# full_schematic.net
KiCad netlist of a schematic drawn in EAGLE
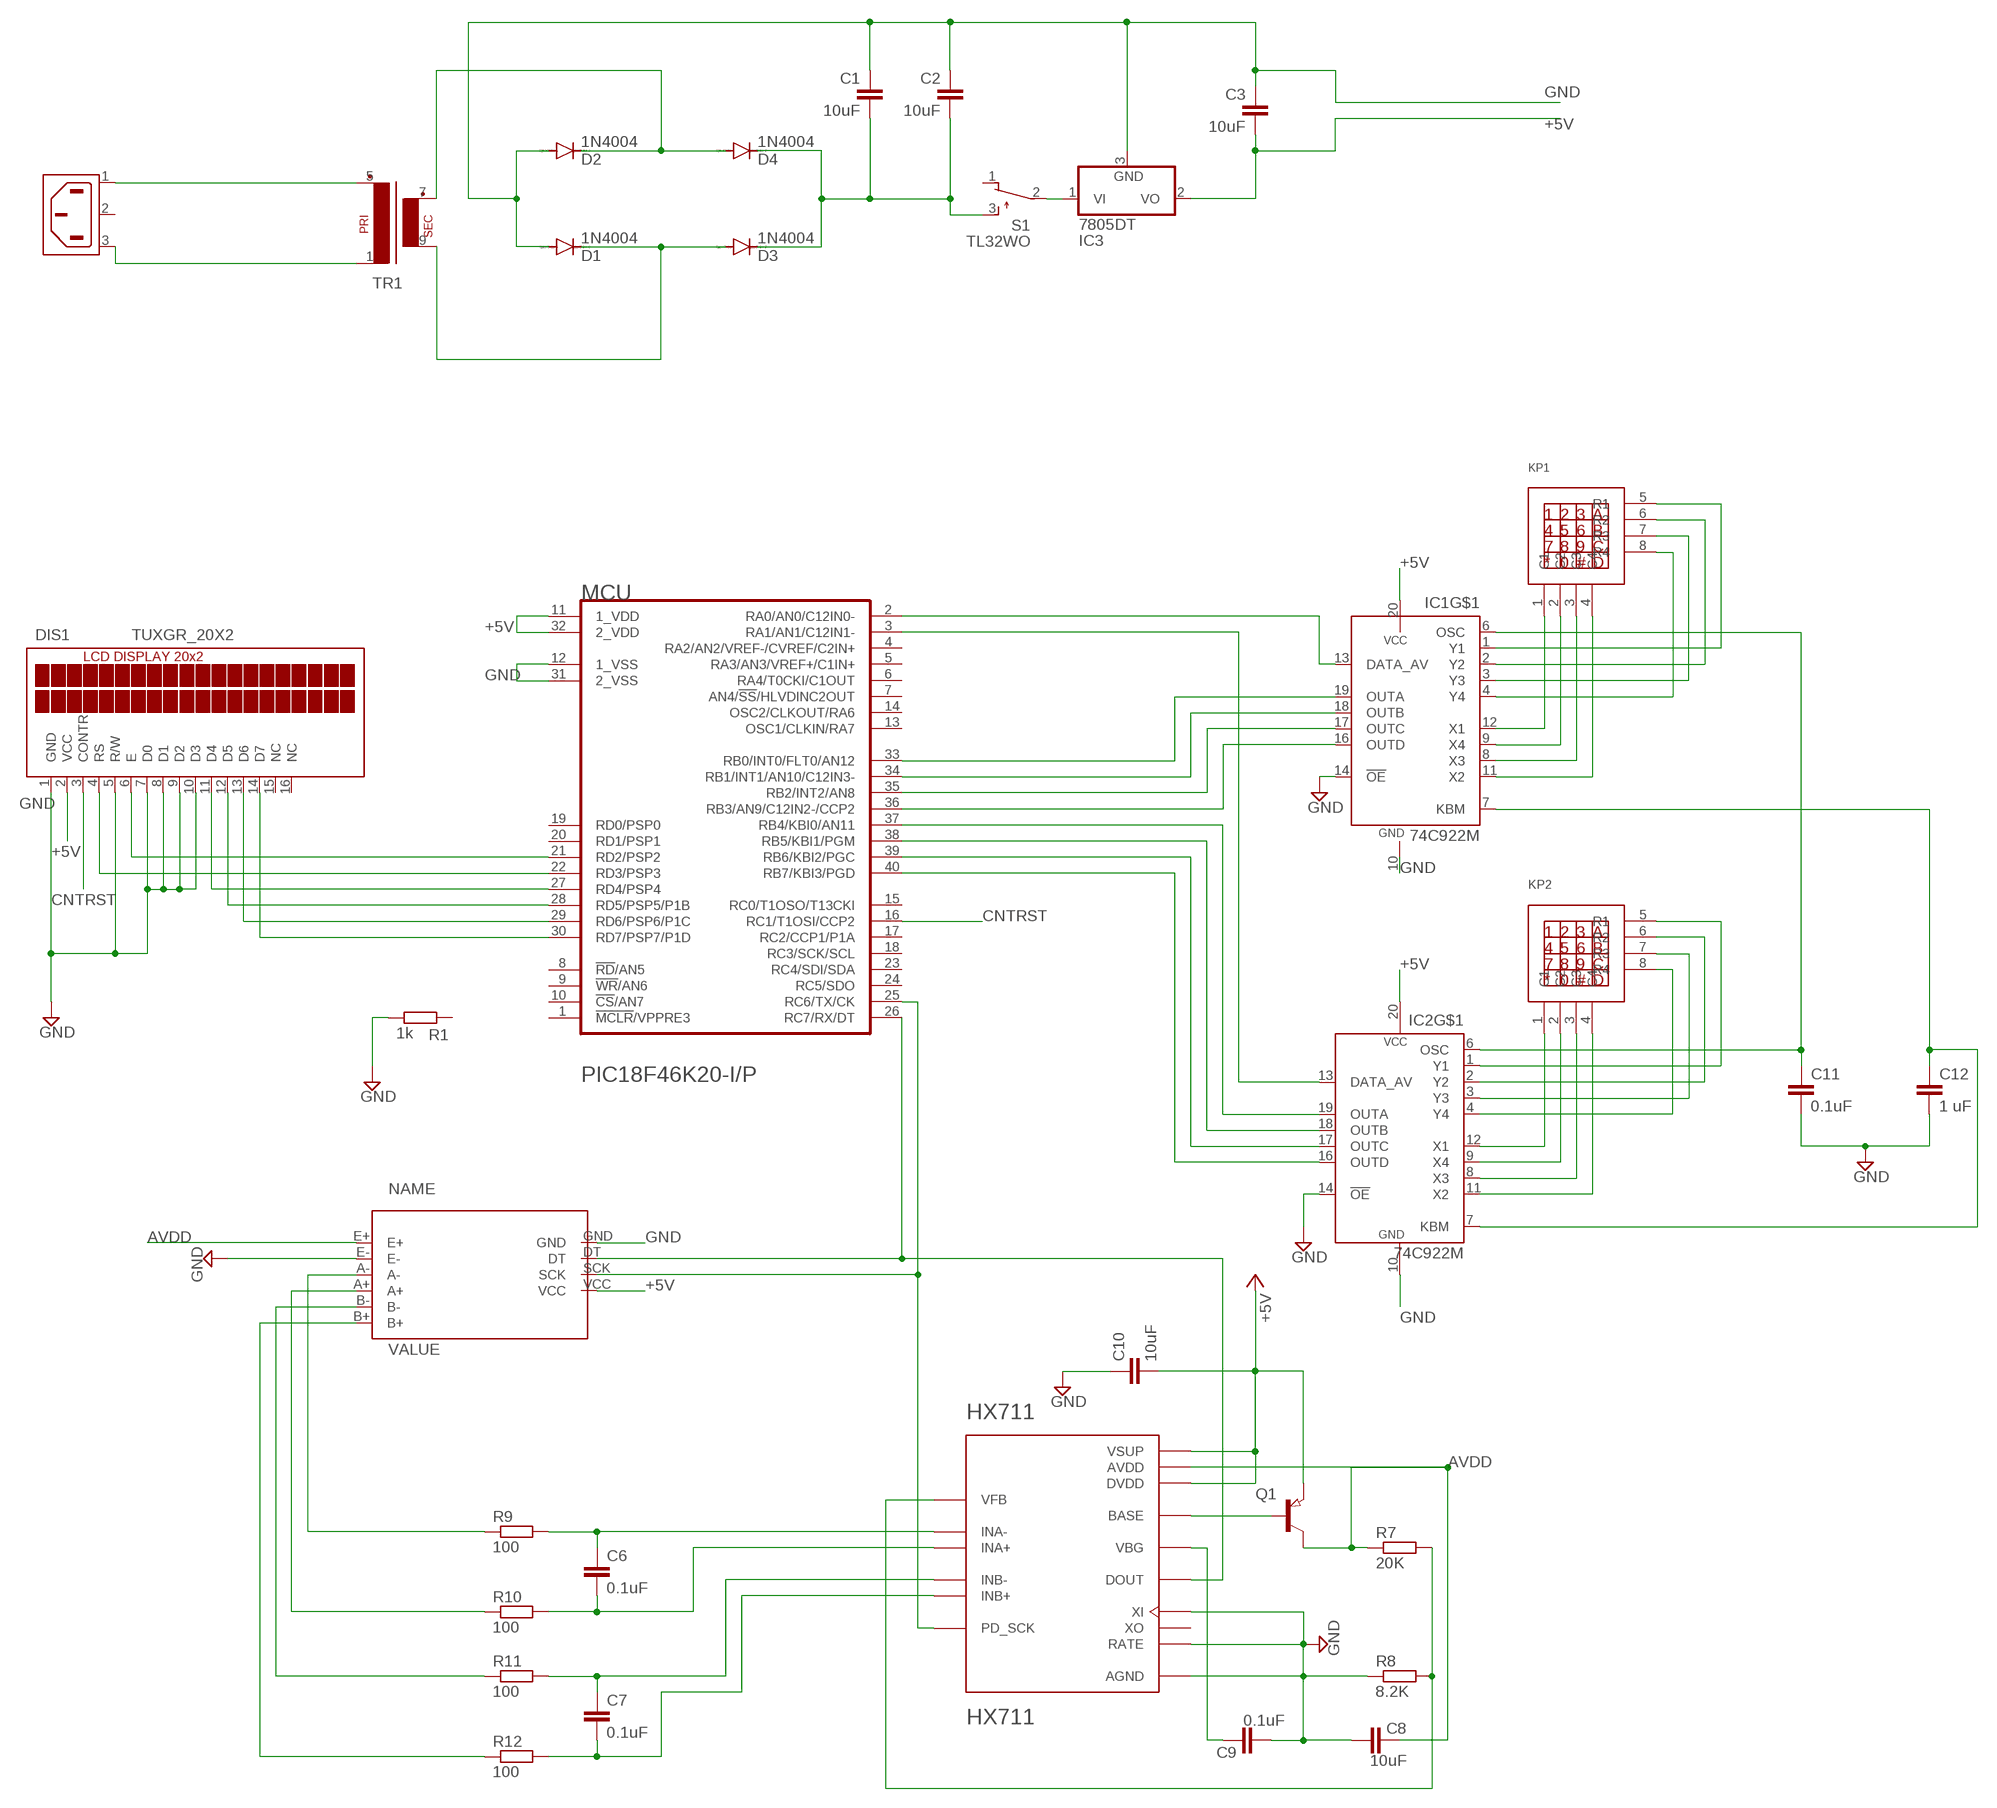
[diagram p0: schematic, sheet 1]

(export (version "E")
  (design (tool "Eeschema 10.0.6"))
  (components
    (comp (ref "C1")
      (value "10uF")
      (footprint "eagle-import:C2.5-2")
      (libsource (lib "eagle-import") (part "C2.5/2"))
    )
    (comp (ref "C2")
      (value "10uF")
      (footprint "eagle-import:C2.5-2")
      (libsource (lib "eagle-import") (part "C2.5/2"))
    )
    (comp (ref "C3")
      (value "10uF")
      (footprint "eagle-import:C2.5-2")
      (libsource (lib "eagle-import") (part "C2.5/2"))
    )
    (comp (ref "C6")
      (value "0.1uF")
      (footprint "eagle-import:C2.5-2")
      (libsource (lib "eagle-import") (part "C2.5/2"))
    )
    (comp (ref "C7")
      (value "0.1uF")
      (footprint "eagle-import:C2.5-2")
      (libsource (lib "eagle-import") (part "C2.5/2"))
    )
    (comp (ref "C8")
      (value "10uF")
      (footprint "eagle-import:C2.5-2")
      (libsource (lib "eagle-import") (part "C2.5/2"))
    )
    (comp (ref "C9")
      (value "0.1uF")
      (footprint "eagle-import:C2.5-2")
      (libsource (lib "eagle-import") (part "C2.5/2"))
    )
    (comp (ref "C10")
      (value "10uF")
      (footprint "eagle-import:C2.5-2")
      (libsource (lib "eagle-import") (part "C2.5/2"))
    )
    (comp (ref "C11")
      (value "0.1uF")
      (footprint "eagle-import:C2.5-2")
      (libsource (lib "eagle-import") (part "C2.5/2"))
    )
    (comp (ref "C12")
      (value "1 uF")
      (footprint "eagle-import:C2.5-2")
      (libsource (lib "eagle-import") (part "C2.5/2"))
    )
    (comp (ref "D1")
      (value "1N4004")
      (footprint "eagle-import:DO41-10")
      (libsource (lib "eagle-import") (part "1N4004"))
    )
    (comp (ref "D2")
      (value "1N4004")
      (footprint "eagle-import:DO41-10")
      (libsource (lib "eagle-import") (part "1N4004"))
    )
    (comp (ref "D3")
      (value "1N4004")
      (footprint "eagle-import:DO41-10")
      (libsource (lib "eagle-import") (part "1N4004"))
    )
    (comp (ref "D4")
      (value "1N4004")
      (footprint "eagle-import:DO41-10")
      (libsource (lib "eagle-import") (part "1N4004"))
    )
    (comp (ref "DIS1")
      (value "TUXGR_20X2")
      (footprint "eagle-import:TUXGR_20X2")
      (libsource (lib "eagle-import") (part "TUXGR_20X2"))
    )
    (comp (ref "HX711")
      (value "HX711")
      (footprint "eagle-import:SOP127P600X180-16N")
      (fields (field (name "MF") "AVIA SEMICONDUCTOR"))
      (libsource (lib "eagle-import") (part "HX711"))
    )
    (comp (ref "HX711MODULE")
      (value "hx")
      (footprint "eagle-import:HX711")
      (libsource (lib "eagle-import") (part "HX711A"))
    )
    (comp (ref "IC1")
      (value "74C922M")
      (footprint "eagle-import:SO20W")
      (libsource (lib "eagle-import") (part "74C922M"))
    )
    (comp (ref "IC2")
      (value "74C922M")
      (footprint "eagle-import:SO20W")
      (libsource (lib "eagle-import") (part "74C922M"))
    )
    (comp (ref "IC3")
      (value "7805DT")
      (footprint "eagle-import:TO252")
      (libsource (lib "eagle-import") (part "78DT05"))
    )
    (comp (ref "KP1")
      (value "KEYPAD4X4")
      (footprint "eagle-import:KEYPAD4X4")
      (libsource (lib "eagle-import") (part "KEYPAD4X4"))
    )
    (comp (ref "KP2")
      (value "KEYPAD4X4")
      (footprint "eagle-import:KEYPAD4X4")
      (libsource (lib "eagle-import") (part "KEYPAD4X4"))
    )
    (comp (ref "MCU")
      (value "MICROCHIP_PIC18F46K20-I-PMICROCHIP_PIC18F46K20-I-P_0_0")
      (footprint "eagle-import:MICROCHIP_PIC18F46K20-I-P_0")
      (fields (field (name "MF") "Microchip") (field (name "MPN") "PIC18F46K20-I/P"))
      (libsource (lib "eagle-import") (part "MICROCHIP_PIC18F46K20-I-PMICROCHIP_PIC18F46K20-I-P_0_0"))
    )
    (comp (ref "Q1")
      (value "PNP-TRANSISTOR_SOT23")
      (footprint "eagle-import:SOT23")
      (libsource (lib "eagle-import") (part "PNP-TRANSISTOR_SOT23"))
    )
    (comp (ref "R1")
      (value "1k")
      (footprint "eagle-import:R0603")
      (libsource (lib "eagle-import") (part "R-EU_R0603"))
    )
    (comp (ref "R7")
      (value "20K")
      (footprint "eagle-import:R0603")
      (libsource (lib "eagle-import") (part "R-EU_R0603"))
    )
    (comp (ref "R8")
      (value "8.2K")
      (footprint "eagle-import:R0603")
      (libsource (lib "eagle-import") (part "R-EU_R0603"))
    )
    (comp (ref "R9")
      (value "100")
      (footprint "eagle-import:R0603")
      (libsource (lib "eagle-import") (part "R-EU_R0603"))
    )
    (comp (ref "R10")
      (value "100")
      (footprint "eagle-import:R0603")
      (libsource (lib "eagle-import") (part "R-EU_R0603"))
    )
    (comp (ref "R11")
      (value "100")
      (footprint "eagle-import:R0603")
      (libsource (lib "eagle-import") (part "R-EU_R0603"))
    )
    (comp (ref "R12")
      (value "100")
      (footprint "eagle-import:R0603")
      (libsource (lib "eagle-import") (part "R-EU_R0603"))
    )
    (comp (ref "S1")
      (value "TL32WO")
      (footprint "eagle-import:TL3XWO")
      (libsource (lib "eagle-import") (part "TL32WO"))
    )
    (comp (ref "TR1")
      (value "EI30-1")
      (footprint "eagle-import:EI30-1")
      (libsource (lib "eagle-import") (part "EI30-1"))
    )
    (comp (ref "X1")
      (value "6ESRM-P")
      (footprint "eagle-import:6ESRM-P")
      (fields (field (name "MF") "TYCO ELECTRONICS"))
      (libsource (lib "eagle-import") (part "6ESRM-P"))
    )
  )
  (nets
    (net (code "1") (name "+5V") (class "Default")
      (node (ref "C10") (pin "2") (pinfunction "2_2") (pintype "passive"))
      (node (ref "C3") (pin "2") (pinfunction "2_2") (pintype "passive"))
      (node (ref "DIS1") (pin "2") (pinfunction "VCC_2") (pintype "power_in"))
      (node (ref "HX711") (pin "1") (pinfunction "VSUP_1") (pintype "power_in"))
      (node (ref "HX711") (pin "16") (pinfunction "DVDD_16") (pintype "power_in"))
      (node (ref "HX711MODULE") (pin "VCC") (pinfunction "VCC_VCC") (pintype "bidirectional"))
      (node (ref "IC1") (pin "20") (pinfunction "VCC_20") (pintype "power_in"))
      (node (ref "IC2") (pin "20") (pinfunction "VCC_20") (pintype "power_in"))
      (node (ref "IC3") (pin "2") (pinfunction "VO_2") (pintype "passive"))
      (node (ref "MCU") (pin "11") (pinfunction "1_VDD_11") (pintype "power_in"))
      (node (ref "MCU") (pin "32") (pinfunction "2_VDD_32") (pintype "power_in"))
      (node (ref "Q1") (pin "2") (pinfunction "E_2") (pintype "passive"))
    )
    (net (code "2") (name "/AVDD") (class "Default")
      (node (ref "C8") (pin "1") (pinfunction "1_1") (pintype "passive"))
      (node (ref "HX711") (pin "3") (pinfunction "AVDD_3") (pintype "power_in"))
      (node (ref "HX711MODULE") (pin "E+") (pinfunction "E+_E+") (pintype "bidirectional"))
      (node (ref "Q1") (pin "3") (pinfunction "C_3") (pintype "passive"))
      (node (ref "R7") (pin "1") (pinfunction "1_1") (pintype "passive"))
    )
    (net (code "3") (name "/CNTRST") (class "Default")
      (node (ref "DIS1") (pin "3") (pinfunction "CONTR_3") (pintype "input"))
      (node (ref "MCU") (pin "16") (pinfunction "RC1/T1OSI/CCP2_16") (pintype "bidirectional"))
    )
    (net (code "4") (name "GND") (class "Default")
      (node (ref "C1") (pin "1") (pinfunction "1_1") (pintype "passive"))
      (node (ref "C10") (pin "1") (pinfunction "1_1") (pintype "passive"))
      (node (ref "C11") (pin "2") (pinfunction "2_2") (pintype "passive"))
      (node (ref "C12") (pin "2") (pinfunction "2_2") (pintype "passive"))
      (node (ref "C2") (pin "1") (pinfunction "1_1") (pintype "passive"))
      (node (ref "C3") (pin "1") (pinfunction "1_1") (pintype "passive"))
      (node (ref "C8") (pin "2") (pinfunction "2_2") (pintype "passive"))
      (node (ref "C9") (pin "2") (pinfunction "2_2") (pintype "passive"))
      (node (ref "D1") (pin "A") (pinfunction "A_A") (pintype "passive"))
      (node (ref "D2") (pin "A") (pinfunction "A_A") (pintype "passive"))
      (node (ref "DIS1") (pin "1") (pinfunction "GND_1") (pintype "power_in"))
      (node (ref "DIS1") (pin "10") (pinfunction "D3_10") (pintype "input"))
      (node (ref "DIS1") (pin "5") (pinfunction "R/W_5") (pintype "input"))
      (node (ref "DIS1") (pin "7") (pinfunction "D0_7") (pintype "input"))
      (node (ref "DIS1") (pin "8") (pinfunction "D1_8") (pintype "input"))
      (node (ref "DIS1") (pin "9") (pinfunction "D2_9") (pintype "input"))
      (node (ref "HX711") (pin "14") (pinfunction "XI_14") (pintype "input"))
      (node (ref "HX711") (pin "15") (pinfunction "RATE_15") (pintype "input"))
      (node (ref "HX711") (pin "5") (pinfunction "AGND_5") (pintype "power_in"))
      (node (ref "HX711MODULE") (pin "E-") (pinfunction "E-_E-") (pintype "bidirectional"))
      (node (ref "HX711MODULE") (pin "GND") (pinfunction "GND_GND") (pintype "bidirectional"))
      (node (ref "IC1") (pin "10") (pinfunction "GND_10") (pintype "power_in"))
      (node (ref "IC1") (pin "14") (pinfunction "~{OE}_14") (pintype "input"))
      (node (ref "IC2") (pin "10") (pinfunction "GND_10") (pintype "power_in"))
      (node (ref "IC2") (pin "14") (pinfunction "~{OE}_14") (pintype "input"))
      (node (ref "IC3") (pin "3") (pinfunction "GND_3") (pintype "passive"))
      (node (ref "MCU") (pin "12") (pinfunction "1_VSS_12") (pintype "power_in"))
      (node (ref "MCU") (pin "31") (pinfunction "2_VSS_31") (pintype "power_in"))
      (node (ref "R1") (pin "1") (pinfunction "1_1") (pintype "passive"))
      (node (ref "R8") (pin "1") (pinfunction "1_1") (pintype "passive"))
    )
    (net (code "5") (name "Net-(DIS1-D4)") (class "Default")
      (node (ref "DIS1") (pin "11") (pinfunction "D4_11") (pintype "input"))
      (node (ref "MCU") (pin "27") (pinfunction "RD4/PSP4_27") (pintype "bidirectional"))
    )
    (net (code "6") (name "Net-(DIS1-D5)") (class "Default")
      (node (ref "DIS1") (pin "12") (pinfunction "D5_12") (pintype "input"))
      (node (ref "MCU") (pin "28") (pinfunction "RD5/PSP5/P1B_28") (pintype "bidirectional"))
    )
    (net (code "7") (name "Net-(DIS1-D6)") (class "Default")
      (node (ref "DIS1") (pin "13") (pinfunction "D6_13") (pintype "input"))
      (node (ref "MCU") (pin "29") (pinfunction "RD6/PSP6/P1C_29") (pintype "bidirectional"))
    )
    (net (code "8") (name "Net-(DIS1-D7)") (class "Default")
      (node (ref "DIS1") (pin "14") (pinfunction "D7_14") (pintype "input"))
      (node (ref "MCU") (pin "30") (pinfunction "RD7/PSP7/P1D_30") (pintype "bidirectional"))
    )
    (net (code "9") (name "Net-(DIS1-E)") (class "Default")
      (node (ref "DIS1") (pin "6") (pinfunction "E_6") (pintype "input"))
      (node (ref "MCU") (pin "21") (pinfunction "RD2/PSP2_21") (pintype "bidirectional"))
    )
    (net (code "10") (name "Net-(DIS1-RS)") (class "Default")
      (node (ref "DIS1") (pin "4") (pinfunction "RS_4") (pintype "input"))
      (node (ref "MCU") (pin "22") (pinfunction "RD3/PSP3_22") (pintype "bidirectional"))
    )
    (net (code "11") (name "Net-(HX711-BASE)") (class "Default")
      (node (ref "HX711") (pin "2") (pinfunction "BASE_2") (pintype "output"))
      (node (ref "Q1") (pin "1") (pinfunction "B_1") (pintype "passive"))
    )
    (net (code "12") (name "Net-(HX711-DOUT)") (class "Default")
      (node (ref "HX711") (pin "12") (pinfunction "DOUT_12") (pintype "output"))
      (node (ref "HX711MODULE") (pin "DT") (pinfunction "DT_DT") (pintype "bidirectional"))
      (node (ref "MCU") (pin "26") (pinfunction "RC7/RX/DT_26") (pintype "bidirectional"))
    )
    (net (code "13") (name "Net-(HX711-INA+)") (class "Default")
      (node (ref "C6") (pin "2") (pinfunction "2_2") (pintype "passive"))
      (node (ref "HX711") (pin "8") (pinfunction "INA+_8") (pintype "input"))
      (node (ref "R10") (pin "2") (pinfunction "2_2") (pintype "passive"))
    )
    (net (code "14") (name "Net-(HX711-INA-)") (class "Default")
      (node (ref "C6") (pin "1") (pinfunction "1_1") (pintype "passive"))
      (node (ref "HX711") (pin "7") (pinfunction "INA-_7") (pintype "input"))
      (node (ref "R9") (pin "2") (pinfunction "2_2") (pintype "passive"))
    )
    (net (code "15") (name "Net-(HX711-INB+)") (class "Default")
      (node (ref "C7") (pin "2") (pinfunction "2_2") (pintype "passive"))
      (node (ref "HX711") (pin "10") (pinfunction "INB+_10") (pintype "input"))
      (node (ref "R12") (pin "2") (pinfunction "2_2") (pintype "passive"))
    )
    (net (code "16") (name "Net-(HX711-INB-)") (class "Default")
      (node (ref "C7") (pin "1") (pinfunction "1_1") (pintype "passive"))
      (node (ref "HX711") (pin "9") (pinfunction "INB-_9") (pintype "input"))
      (node (ref "R11") (pin "2") (pinfunction "2_2") (pintype "passive"))
    )
    (net (code "17") (name "Net-(HX711-PD_SCK)") (class "Default")
      (node (ref "HX711") (pin "11") (pinfunction "PD_SCK_11") (pintype "input"))
      (node (ref "HX711MODULE") (pin "SCK") (pinfunction "SCK_SCK") (pintype "bidirectional"))
      (node (ref "MCU") (pin "25") (pinfunction "RC6/TX/CK_25") (pintype "bidirectional"))
    )
    (net (code "18") (name "Net-(HX711-VBG)") (class "Default")
      (node (ref "C9") (pin "1") (pinfunction "1_1") (pintype "passive"))
      (node (ref "HX711") (pin "6") (pinfunction "VBG_6") (pintype "output"))
    )
    (net (code "19") (name "Net-(HX711-VFB)") (class "Default")
      (node (ref "HX711") (pin "4") (pinfunction "VFB_4") (pintype "input"))
      (node (ref "R7") (pin "2") (pinfunction "2_2") (pintype "passive"))
      (node (ref "R8") (pin "2") (pinfunction "2_2") (pintype "passive"))
    )
    (net (code "20") (name "Net-(HX711MODULE-PadA+)") (class "Default")
      (node (ref "HX711MODULE") (pin "A+") (pinfunction "A+_A+") (pintype "bidirectional"))
      (node (ref "R10") (pin "1") (pinfunction "1_1") (pintype "passive"))
    )
    (net (code "21") (name "Net-(HX711MODULE-PadA-)") (class "Default")
      (node (ref "HX711MODULE") (pin "A-") (pinfunction "A-_A-") (pintype "bidirectional"))
      (node (ref "R9") (pin "1") (pinfunction "1_1") (pintype "passive"))
    )
    (net (code "22") (name "Net-(HX711MODULE-PadB+)") (class "Default")
      (node (ref "HX711MODULE") (pin "B+") (pinfunction "B+_B+") (pintype "bidirectional"))
      (node (ref "R12") (pin "1") (pinfunction "1_1") (pintype "passive"))
    )
    (net (code "23") (name "Net-(HX711MODULE-PadB-)") (class "Default")
      (node (ref "HX711MODULE") (pin "B-") (pinfunction "B-_B-") (pintype "bidirectional"))
      (node (ref "R11") (pin "1") (pinfunction "1_1") (pintype "passive"))
    )
    (net (code "24") (name "Net-(IC1A-DATA_AV)") (class "Default")
      (node (ref "IC1") (pin "13") (pinfunction "DATA_AV_13") (pintype "output"))
      (node (ref "MCU") (pin "2") (pinfunction "RA0/AN0/C12IN0-_2") (pintype "bidirectional"))
    )
    (net (code "25") (name "Net-(IC1A-KBM)") (class "Default")
      (node (ref "C12") (pin "1") (pinfunction "1_1") (pintype "passive"))
      (node (ref "IC1") (pin "7") (pinfunction "KBM_7") (pintype "input"))
      (node (ref "IC2") (pin "7") (pinfunction "KBM_7") (pintype "input"))
    )
    (net (code "26") (name "Net-(IC1A-OSC)") (class "Default")
      (node (ref "C11") (pin "1") (pinfunction "1_1") (pintype "passive"))
      (node (ref "IC1") (pin "6") (pinfunction "OSC_6") (pintype "input"))
      (node (ref "IC2") (pin "6") (pinfunction "OSC_6") (pintype "input"))
    )
    (net (code "27") (name "Net-(IC1A-OUTA)") (class "Default")
      (node (ref "IC1") (pin "19") (pinfunction "OUTA_19") (pintype "output"))
      (node (ref "MCU") (pin "33") (pinfunction "RB0/INT0/FLT0/AN12_33") (pintype "bidirectional"))
    )
    (net (code "28") (name "Net-(IC1A-OUTB)") (class "Default")
      (node (ref "IC1") (pin "18") (pinfunction "OUTB_18") (pintype "output"))
      (node (ref "MCU") (pin "34") (pinfunction "RB1/INT1/AN10/C12IN3-_34") (pintype "bidirectional"))
    )
    (net (code "29") (name "Net-(IC1A-OUTC)") (class "Default")
      (node (ref "IC1") (pin "17") (pinfunction "OUTC_17") (pintype "output"))
      (node (ref "MCU") (pin "35") (pinfunction "RB2/INT2/AN8_35") (pintype "bidirectional"))
    )
    (net (code "30") (name "Net-(IC1A-OUTD)") (class "Default")
      (node (ref "IC1") (pin "16") (pinfunction "OUTD_16") (pintype "output"))
      (node (ref "MCU") (pin "36") (pinfunction "RB3/AN9/C12IN2-/CCP2_36") (pintype "bidirectional"))
    )
    (net (code "31") (name "Net-(IC1A-X1)") (class "Default")
      (node (ref "IC1") (pin "12") (pinfunction "X1_12") (pintype "input"))
      (node (ref "KP1") (pin "1") (pinfunction "C1_1") (pintype "bidirectional"))
    )
    (net (code "32") (name "Net-(IC1A-X2)") (class "Default")
      (node (ref "IC1") (pin "11") (pinfunction "X2_11") (pintype "input"))
      (node (ref "KP1") (pin "4") (pinfunction "C4_4") (pintype "bidirectional"))
    )
    (net (code "33") (name "Net-(IC1A-X3)") (class "Default")
      (node (ref "IC1") (pin "8") (pinfunction "X3_8") (pintype "input"))
      (node (ref "KP1") (pin "3") (pinfunction "C3_3") (pintype "bidirectional"))
    )
    (net (code "34") (name "Net-(IC1A-X4)") (class "Default")
      (node (ref "IC1") (pin "9") (pinfunction "X4_9") (pintype "input"))
      (node (ref "KP1") (pin "2") (pinfunction "C2_2") (pintype "bidirectional"))
    )
    (net (code "35") (name "Net-(IC1A-Y1)") (class "Default")
      (node (ref "IC1") (pin "1") (pinfunction "Y1_1") (pintype "input"))
      (node (ref "KP1") (pin "5") (pinfunction "R1_5") (pintype "bidirectional"))
    )
    (net (code "36") (name "Net-(IC1A-Y2)") (class "Default")
      (node (ref "IC1") (pin "2") (pinfunction "Y2_2") (pintype "input"))
      (node (ref "KP1") (pin "6") (pinfunction "R2_6") (pintype "bidirectional"))
    )
    (net (code "37") (name "Net-(IC1A-Y3)") (class "Default")
      (node (ref "IC1") (pin "3") (pinfunction "Y3_3") (pintype "input"))
      (node (ref "KP1") (pin "7") (pinfunction "R3_7") (pintype "bidirectional"))
    )
    (net (code "38") (name "Net-(IC1A-Y4)") (class "Default")
      (node (ref "IC1") (pin "4") (pinfunction "Y4_4") (pintype "input"))
      (node (ref "KP1") (pin "8") (pinfunction "R4_8") (pintype "bidirectional"))
    )
    (net (code "39") (name "Net-(IC2A-DATA_AV)") (class "Default")
      (node (ref "IC2") (pin "13") (pinfunction "DATA_AV_13") (pintype "output"))
      (node (ref "MCU") (pin "3") (pinfunction "RA1/AN1/C12IN1-_3") (pintype "bidirectional"))
    )
    (net (code "40") (name "Net-(IC2A-OUTA)") (class "Default")
      (node (ref "IC2") (pin "19") (pinfunction "OUTA_19") (pintype "output"))
      (node (ref "MCU") (pin "37") (pinfunction "RB4/KBI0/AN11_37") (pintype "bidirectional"))
    )
    (net (code "41") (name "Net-(IC2A-OUTB)") (class "Default")
      (node (ref "IC2") (pin "18") (pinfunction "OUTB_18") (pintype "output"))
      (node (ref "MCU") (pin "38") (pinfunction "RB5/KBI1/PGM_38") (pintype "bidirectional"))
    )
    (net (code "42") (name "Net-(IC2A-OUTC)") (class "Default")
      (node (ref "IC2") (pin "17") (pinfunction "OUTC_17") (pintype "output"))
      (node (ref "MCU") (pin "39") (pinfunction "RB6/KBI2/PGC_39") (pintype "bidirectional"))
    )
    (net (code "43") (name "Net-(IC2A-OUTD)") (class "Default")
      (node (ref "IC2") (pin "16") (pinfunction "OUTD_16") (pintype "output"))
      (node (ref "MCU") (pin "40") (pinfunction "RB7/KBI3/PGD_40") (pintype "bidirectional"))
    )
    (net (code "44") (name "Net-(IC2A-X1)") (class "Default")
      (node (ref "IC2") (pin "12") (pinfunction "X1_12") (pintype "input"))
      (node (ref "KP2") (pin "1") (pinfunction "C1_1") (pintype "bidirectional"))
    )
    (net (code "45") (name "Net-(IC2A-X2)") (class "Default")
      (node (ref "IC2") (pin "11") (pinfunction "X2_11") (pintype "input"))
      (node (ref "KP2") (pin "4") (pinfunction "C4_4") (pintype "bidirectional"))
    )
    (net (code "46") (name "Net-(IC2A-X3)") (class "Default")
      (node (ref "IC2") (pin "8") (pinfunction "X3_8") (pintype "input"))
      (node (ref "KP2") (pin "3") (pinfunction "C3_3") (pintype "bidirectional"))
    )
    (net (code "47") (name "Net-(IC2A-X4)") (class "Default")
      (node (ref "IC2") (pin "9") (pinfunction "X4_9") (pintype "input"))
      (node (ref "KP2") (pin "2") (pinfunction "C2_2") (pintype "bidirectional"))
    )
    (net (code "48") (name "Net-(IC2A-Y1)") (class "Default")
      (node (ref "IC2") (pin "1") (pinfunction "Y1_1") (pintype "input"))
      (node (ref "KP2") (pin "5") (pinfunction "R1_5") (pintype "bidirectional"))
    )
    (net (code "49") (name "Net-(IC2A-Y2)") (class "Default")
      (node (ref "IC2") (pin "2") (pinfunction "Y2_2") (pintype "input"))
      (node (ref "KP2") (pin "6") (pinfunction "R2_6") (pintype "bidirectional"))
    )
    (net (code "50") (name "Net-(IC2A-Y3)") (class "Default")
      (node (ref "IC2") (pin "3") (pinfunction "Y3_3") (pintype "input"))
      (node (ref "KP2") (pin "7") (pinfunction "R3_7") (pintype "bidirectional"))
    )
    (net (code "51") (name "Net-(IC2A-Y4)") (class "Default")
      (node (ref "IC2") (pin "4") (pinfunction "Y4_4") (pintype "input"))
      (node (ref "KP2") (pin "8") (pinfunction "R4_8") (pintype "bidirectional"))
    )
    (net (code "52") (name "Net-(IC3-VI)") (class "Default")
      (node (ref "IC3") (pin "1") (pinfunction "VI_1") (pintype "input"))
      (node (ref "S1") (pin "2") (pinfunction "P_2") (pintype "passive"))
    )
    (net (code "53") (name "Net-(S1-S)") (class "Default")
      (node (ref "C1") (pin "2") (pinfunction "2_2") (pintype "passive"))
      (node (ref "C2") (pin "2") (pinfunction "2_2") (pintype "passive"))
      (node (ref "D3") (pin "C") (pinfunction "C_C") (pintype "passive"))
      (node (ref "D4") (pin "C") (pinfunction "C_C") (pintype "passive"))
      (node (ref "S1") (pin "3") (pinfunction "S_3") (pintype "passive"))
    )
    (net (code "54") (name "Net-(TR1-P1)") (class "Default")
      (node (ref "TR1") (pin "1") (pinfunction "P1_1") (pintype "passive"))
      (node (ref "X1") (pin "3") (pinfunction "AC2_3") (pintype "passive"))
    )
    (net (code "55") (name "Net-(TR1-P2)") (class "Default")
      (node (ref "TR1") (pin "5") (pinfunction "P2_5") (pintype "passive"))
      (node (ref "X1") (pin "1") (pinfunction "AC1_1") (pintype "passive"))
    )
    (net (code "56") (name "Net-(TR1-S3)") (class "Default")
      (node (ref "D2") (pin "C") (pinfunction "C_C") (pintype "passive"))
      (node (ref "D4") (pin "A") (pinfunction "A_A") (pintype "passive"))
      (node (ref "TR1") (pin "7") (pinfunction "S3_7") (pintype "passive"))
    )
    (net (code "57") (name "Net-(TR1-S4)") (class "Default")
      (node (ref "D1") (pin "C") (pinfunction "C_C") (pintype "passive"))
      (node (ref "D3") (pin "A") (pinfunction "A_A") (pintype "passive"))
      (node (ref "TR1") (pin "9") (pinfunction "S4_9") (pintype "passive"))
    )
    (net (code "58") (name "unconnected-(DIS1-NC-Pad15)") (class "Default")
      (node (ref "DIS1") (pin "15") (pinfunction "NC_15") (pintype "no_connect"))
    )
    (net (code "59") (name "unconnected-(DIS1-NC-Pad16)") (class "Default")
      (node (ref "DIS1") (pin "16") (pinfunction "NC_16") (pintype "no_connect"))
    )
    (net (code "60") (name "unconnected-(HX711-XO-Pad13)") (class "Default")
      (node (ref "HX711") (pin "13") (pinfunction "XO_13") (pintype "output"))
    )
    (net (code "61") (name "unconnected-(MCU-AN4{slash}~{SS}{slash}HLVDINC2OUT-Pad7)") (class "Default")
      (node (ref "MCU") (pin "7") (pinfunction "AN4/~{SS}/HLVDINC2OUT_7") (pintype "bidirectional"))
    )
    (net (code "62") (name "unconnected-(MCU-OSC1{slash}CLKIN{slash}RA7-Pad13)") (class "Default")
      (node (ref "MCU") (pin "13") (pinfunction "OSC1/CLKIN/RA7_13") (pintype "bidirectional"))
    )
    (net (code "63") (name "unconnected-(MCU-OSC2{slash}CLKOUT{slash}RA6-Pad14)") (class "Default")
      (node (ref "MCU") (pin "14") (pinfunction "OSC2/CLKOUT/RA6_14") (pintype "bidirectional"))
    )
    (net (code "64") (name "unconnected-(MCU-RA2{slash}AN2{slash}VREF-{slash}CVREF{slash}C2IN+-Pad4)") (class "Default")
      (node (ref "MCU") (pin "4") (pinfunction "RA2/AN2/VREF-/CVREF/C2IN+_4") (pintype "bidirectional"))
    )
    (net (code "65") (name "unconnected-(MCU-RA3{slash}AN3{slash}VREF+{slash}C1IN+-Pad5)") (class "Default")
      (node (ref "MCU") (pin "5") (pinfunction "RA3/AN3/VREF+/C1IN+_5") (pintype "bidirectional"))
    )
    (net (code "66") (name "unconnected-(MCU-RA4{slash}T0CKI{slash}C1OUT-Pad6)") (class "Default")
      (node (ref "MCU") (pin "6") (pinfunction "RA4/T0CKI/C1OUT_6") (pintype "bidirectional"))
    )
    (net (code "67") (name "unconnected-(MCU-RC0{slash}T1OSO{slash}T13CKI-Pad15)") (class "Default")
      (node (ref "MCU") (pin "15") (pinfunction "RC0/T1OSO/T13CKI_15") (pintype "bidirectional"))
    )
    (net (code "68") (name "unconnected-(MCU-RC2{slash}CCP1{slash}P1A-Pad17)") (class "Default")
      (node (ref "MCU") (pin "17") (pinfunction "RC2/CCP1/P1A_17") (pintype "bidirectional"))
    )
    (net (code "69") (name "unconnected-(MCU-RC3{slash}SCK{slash}SCL-Pad18)") (class "Default")
      (node (ref "MCU") (pin "18") (pinfunction "RC3/SCK/SCL_18") (pintype "bidirectional"))
    )
    (net (code "70") (name "unconnected-(MCU-RC4{slash}SDI{slash}SDA-Pad23)") (class "Default")
      (node (ref "MCU") (pin "23") (pinfunction "RC4/SDI/SDA_23") (pintype "bidirectional"))
    )
    (net (code "71") (name "unconnected-(MCU-RC5{slash}SDO-Pad24)") (class "Default")
      (node (ref "MCU") (pin "24") (pinfunction "RC5/SDO_24") (pintype "bidirectional"))
    )
    (net (code "72") (name "unconnected-(MCU-RD0{slash}PSP0-Pad19)") (class "Default")
      (node (ref "MCU") (pin "19") (pinfunction "RD0/PSP0_19") (pintype "bidirectional"))
    )
    (net (code "73") (name "unconnected-(MCU-RD1{slash}PSP1-Pad20)") (class "Default")
      (node (ref "MCU") (pin "20") (pinfunction "RD1/PSP1_20") (pintype "bidirectional"))
    )
    (net (code "74") (name "unconnected-(MCU-~{CS}{slash}AN7-Pad10)") (class "Default")
      (node (ref "MCU") (pin "10") (pinfunction "~{CS}/AN7_10") (pintype "bidirectional"))
    )
    (net (code "75") (name "unconnected-(MCU-~{MCLR}{slash}VPPRE3-Pad1)") (class "Default")
      (node (ref "MCU") (pin "1") (pinfunction "~{MCLR}/VPPRE3_1") (pintype "input"))
    )
    (net (code "76") (name "unconnected-(MCU-~{RD}{slash}AN5-Pad8)") (class "Default")
      (node (ref "MCU") (pin "8") (pinfunction "~{RD}/AN5_8") (pintype "bidirectional"))
    )
    (net (code "77") (name "unconnected-(MCU-~{WR}{slash}AN6-Pad9)") (class "Default")
      (node (ref "MCU") (pin "9") (pinfunction "~{WR}/AN6_9") (pintype "bidirectional"))
    )
    (net (code "78") (name "unconnected-(R1-Pad2)") (class "Default")
      (node (ref "R1") (pin "2") (pinfunction "2_2") (pintype "passive"))
    )
    (net (code "79") (name "unconnected-(S1-O-Pad1)") (class "Default")
      (node (ref "S1") (pin "1") (pinfunction "O_1") (pintype "passive"))
    )
    (net (code "80") (name "unconnected-(X1-SH-Pad2)") (class "Default")
      (node (ref "X1") (pin "2") (pinfunction "SH_2") (pintype "passive"))
    )
  )
)
